# NTC.net
KiCad netlist of a schematic drawn in Altium Designer
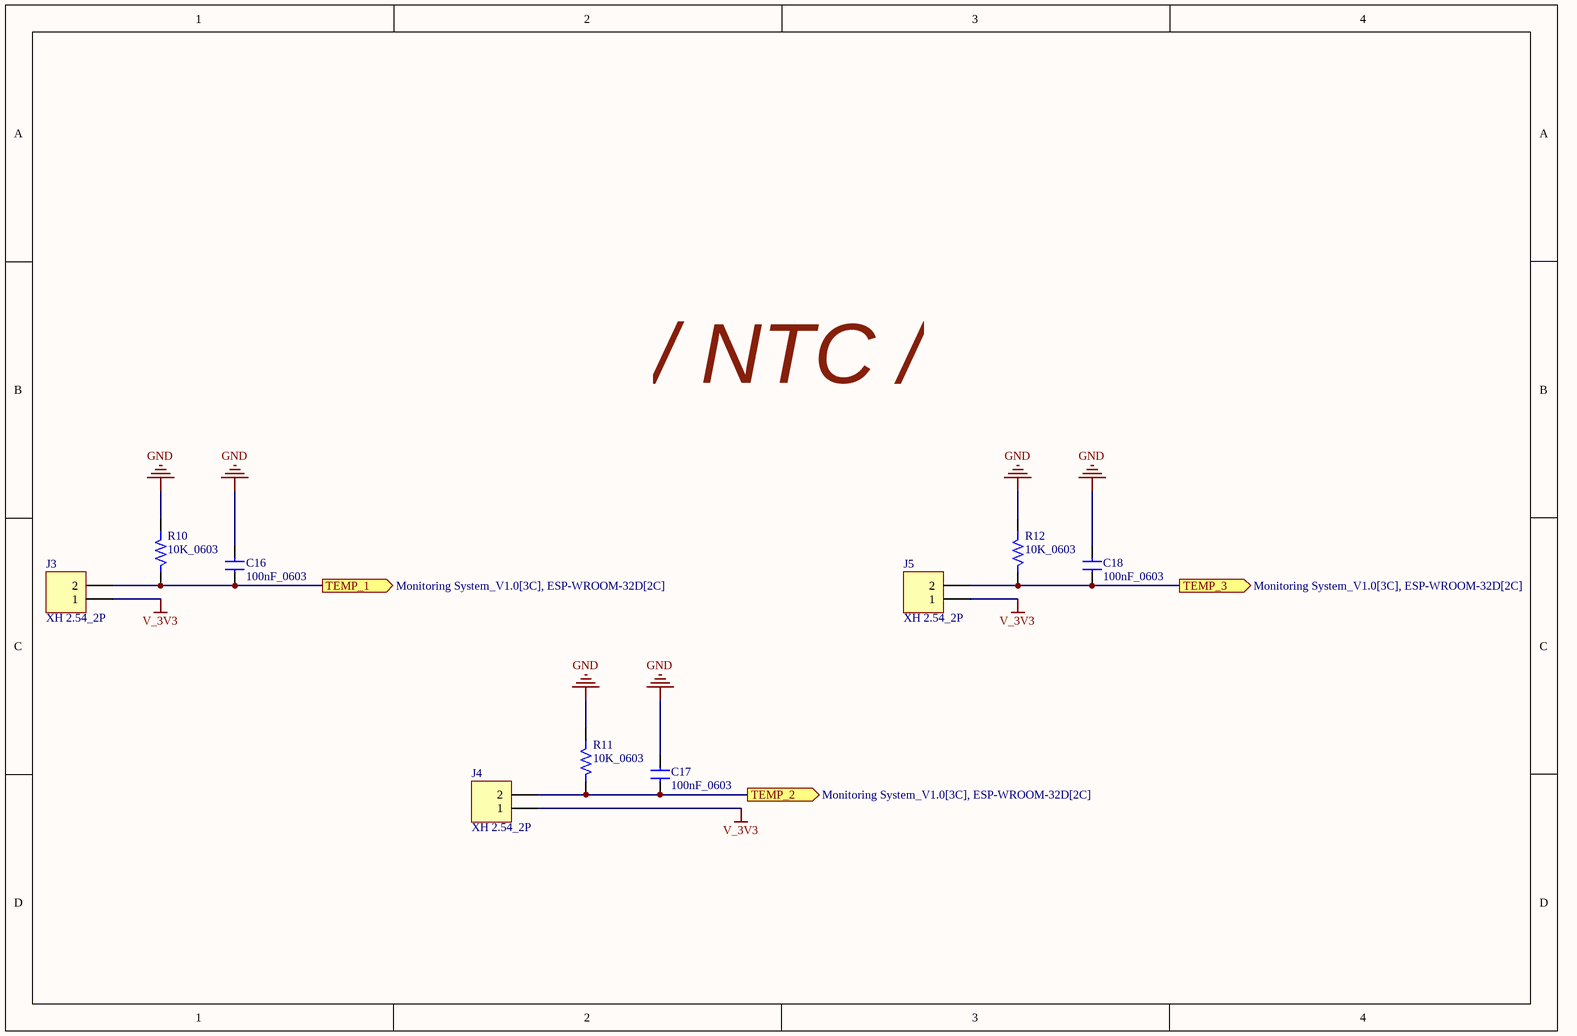
[diagram p0: NTC.SchDoc]

(export (version "E")
  (design (tool "Eeschema 10.0.6"))
  (components
    (comp (ref "C16")
      (value "100nF_0603")
      (footprint "CN-SMD-0603")
      (description "Cap SMD, 0.06x0.03 inch, 1.55x0.85 mm - 1608")
      (libsource (lib "LYAM_LIB") (part "CAP 0603 104"))
    )
    (comp (ref "C17")
      (value "100nF_0603")
      (footprint "CN-SMD-0603")
      (description "Cap SMD, 0.06x0.03 inch, 1.55x0.85 mm - 1608")
      (libsource (lib "LYAM_LIB") (part "CAP 0603 104"))
    )
    (comp (ref "C18")
      (value "100nF_0603")
      (footprint "CN-SMD-0603")
      (description "Cap SMD, 0.06x0.03 inch, 1.55x0.85 mm - 1608")
      (libsource (lib "LYAM_LIB") (part "CAP 0603 104"))
    )
    (comp (ref "J3")
      (value "XH 2.54_2P")
      (footprint "Header2")
      (libsource (lib "LYAM_LIB") (part "XH 2.54_2P"))
    )
    (comp (ref "J4")
      (value "XH 2.54_2P")
      (footprint "Header2")
      (libsource (lib "LYAM_LIB") (part "XH 2.54_2P"))
    )
    (comp (ref "J5")
      (value "XH 2.54_2P")
      (footprint "Header2")
      (libsource (lib "LYAM_LIB") (part "XH 2.54_2P"))
    )
    (comp (ref "R10")
      (value "10K_0603")
      (footprint "RES-SMD-0603")
      (description "Resistor SMD, 0.06x0.03 inch, 1.55x0.85 mm - 1608, 1/10W")
      (libsource (lib "LYAM_LIB") (part "RES 0603 10K"))
    )
    (comp (ref "R11")
      (value "10K_0603")
      (footprint "RES-SMD-0603")
      (description "Resistor SMD, 0.06x0.03 inch, 1.55x0.85 mm - 1608, 1/10W")
      (libsource (lib "LYAM_LIB") (part "RES 0603 10K"))
    )
    (comp (ref "R12")
      (value "10K_0603")
      (footprint "RES-SMD-0603")
      (description "Resistor SMD, 0.06x0.03 inch, 1.55x0.85 mm - 1608, 1/10W")
      (libsource (lib "LYAM_LIB") (part "RES 0603 10K"))
    )
  )
  (nets
    (net (code "1") (name "/TEMP_1") (class "Default")
      (node (ref "C16") (pin "1") (pinfunction "1_1") (pintype "passive"))
      (node (ref "J3") (pin "2") (pinfunction "2_2") (pintype "passive"))
      (node (ref "R10") (pin "1") (pinfunction "1_1") (pintype "passive"))
    )
    (net (code "2") (name "/TEMP_2") (class "Default")
      (node (ref "C17") (pin "1") (pinfunction "1_1") (pintype "passive"))
      (node (ref "J4") (pin "2") (pinfunction "2_2") (pintype "passive"))
      (node (ref "R11") (pin "1") (pinfunction "1_1") (pintype "passive"))
    )
    (net (code "3") (name "/TEMP_3") (class "Default")
      (node (ref "C18") (pin "1") (pinfunction "1_1") (pintype "passive"))
      (node (ref "J5") (pin "2") (pinfunction "2_2") (pintype "passive"))
      (node (ref "R12") (pin "1") (pinfunction "1_1") (pintype "passive"))
    )
    (net (code "4") (name "GND") (class "Default")
      (node (ref "C16") (pin "2") (pinfunction "2_2") (pintype "passive"))
      (node (ref "C17") (pin "2") (pinfunction "2_2") (pintype "passive"))
      (node (ref "C18") (pin "2") (pinfunction "2_2") (pintype "passive"))
      (node (ref "R10") (pin "2") (pinfunction "2_2") (pintype "passive"))
      (node (ref "R11") (pin "2") (pinfunction "2_2") (pintype "passive"))
      (node (ref "R12") (pin "2") (pinfunction "2_2") (pintype "passive"))
    )
    (net (code "5") (name "V_3V3") (class "Default")
      (node (ref "J3") (pin "1") (pinfunction "1_1") (pintype "passive"))
      (node (ref "J4") (pin "1") (pinfunction "1_1") (pintype "passive"))
      (node (ref "J5") (pin "1") (pinfunction "1_1") (pintype "passive"))
    )
  )
)
